# board.net
KiCad netlist of a schematic drawn in EasyEDA Pro
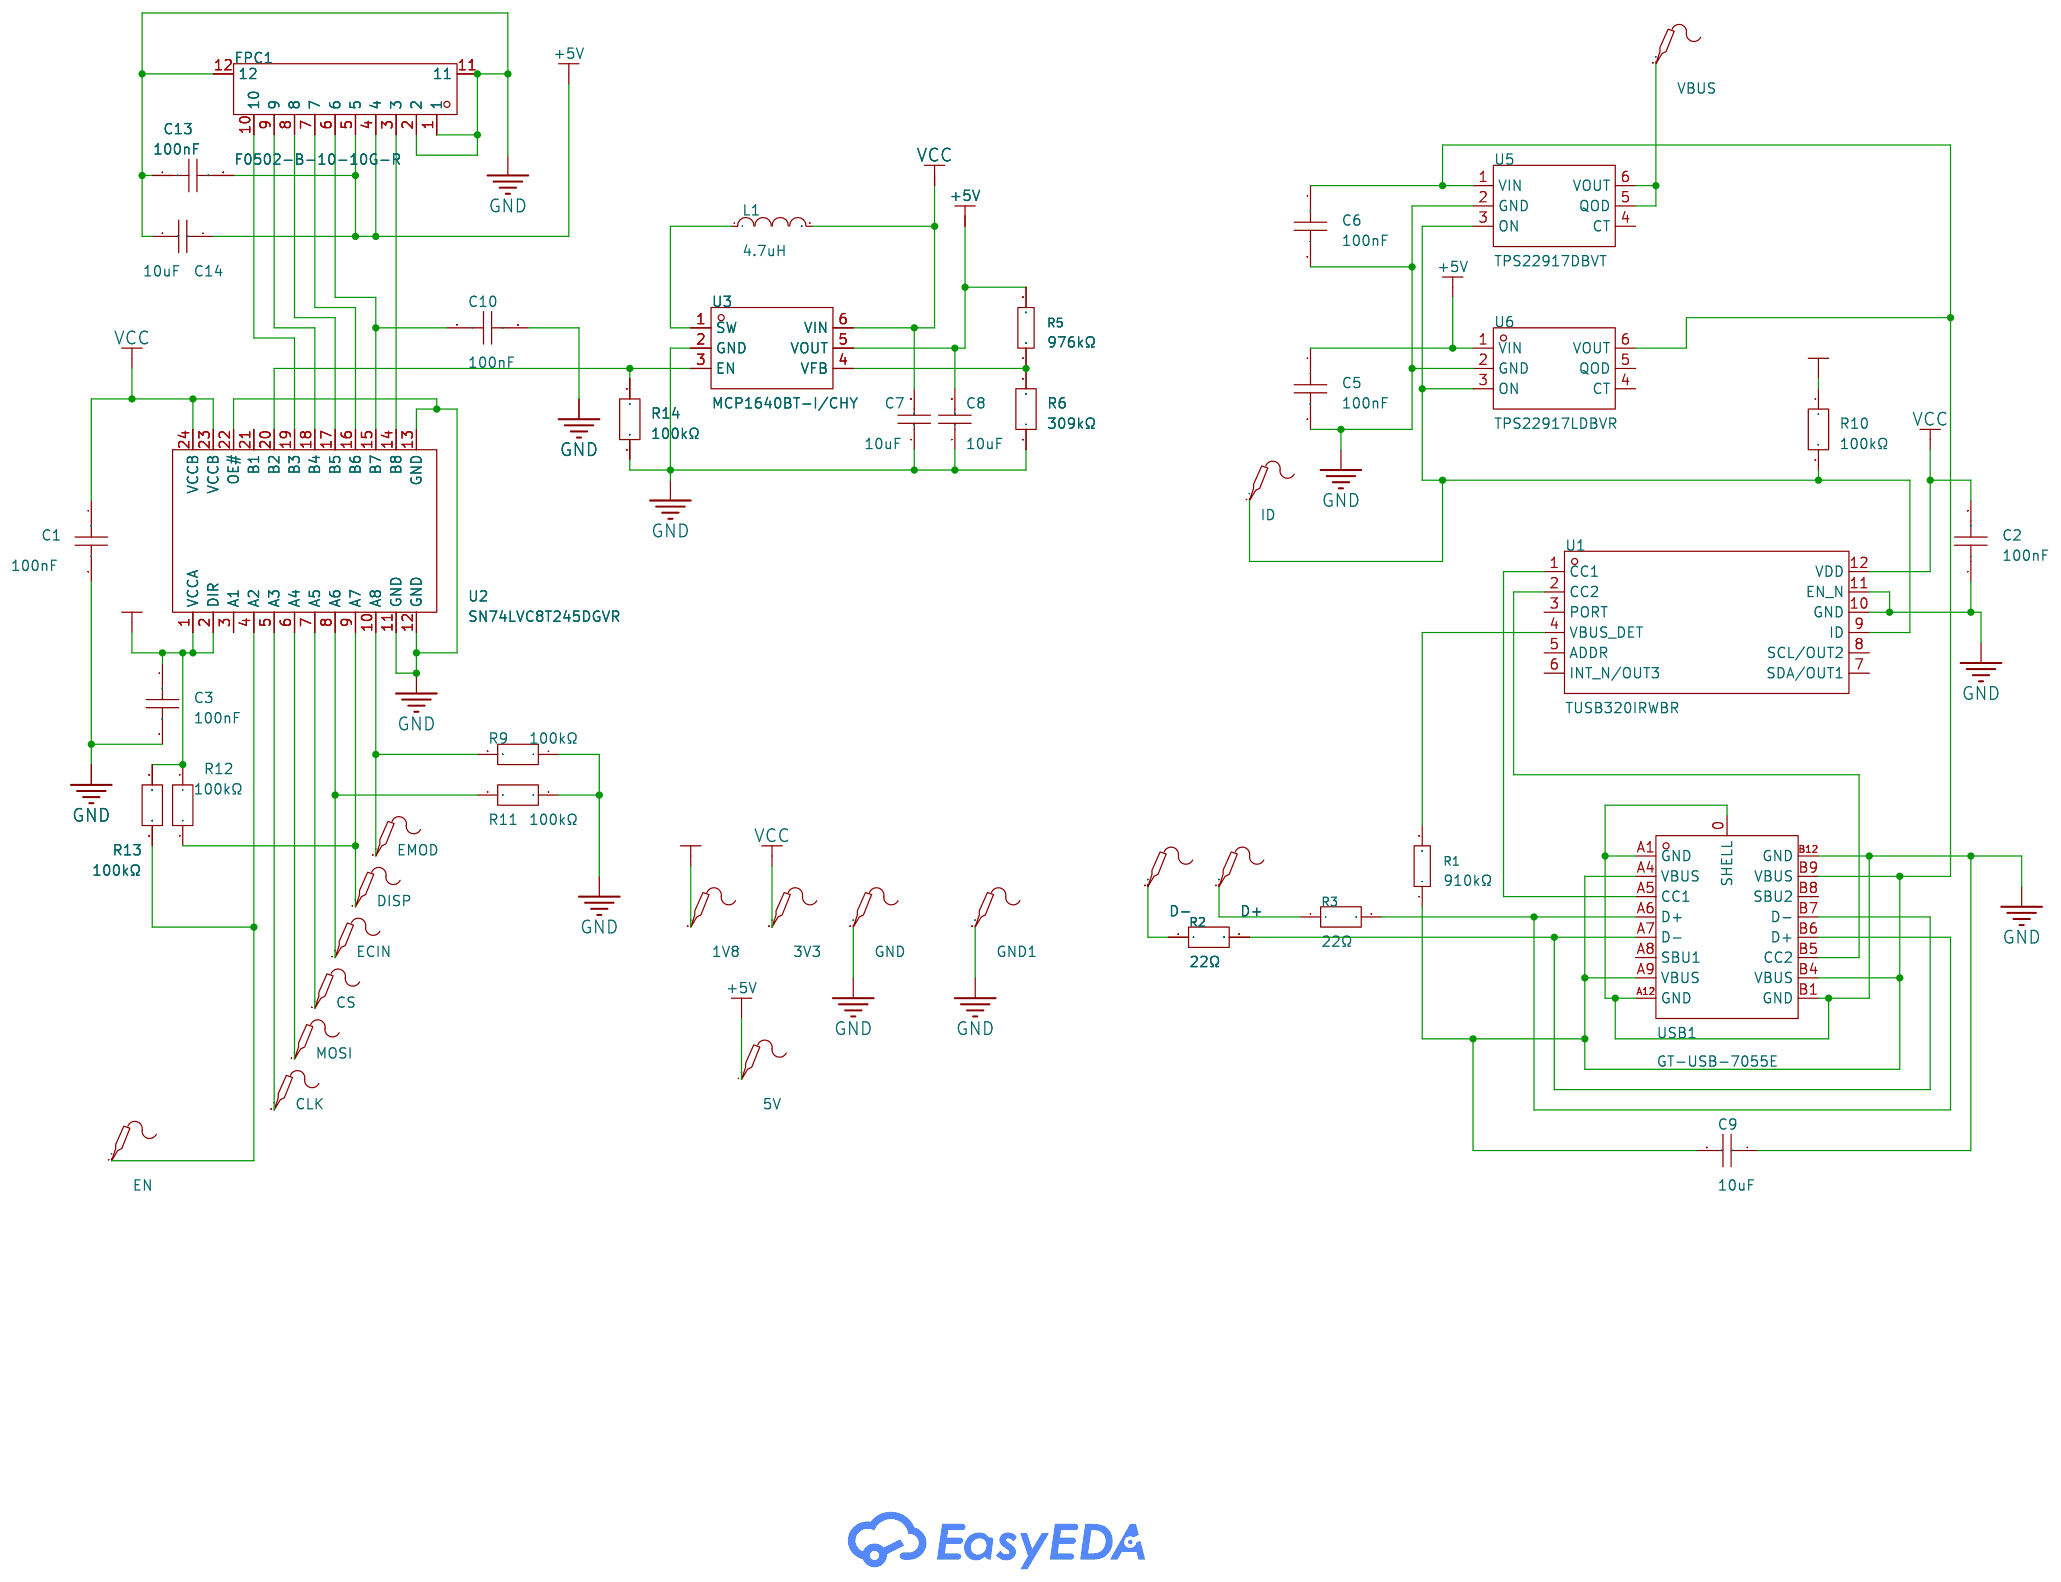
[diagram p0: schematic sheet]

(export (version "E")
  (design (tool "Eeschema 10.0.6"))
  (components
    (comp (ref "1V8")
      (value "~")
      (footprint "easyedapro:Test-Point-0.5mm")
      (description "Test Point 测试点")
      (libsource (lib "easyedapro") (part "Test-Point"))
    )
    (comp (ref "3V3")
      (value "~")
      (footprint "easyedapro:Test-Point-0.5mm")
      (description "Test Point 测试点")
      (libsource (lib "easyedapro") (part "Test-Point"))
    )
    (comp (ref "5V")
      (value "~")
      (footprint "easyedapro:Test-Point-0.5mm")
      (description "Test Point 测试点")
      (libsource (lib "easyedapro") (part "Test-Point"))
    )
    (comp (ref "C1")
      (value "100nF")
      (footprint "easyedapro:C0402")
      (description "Capacitance:100nF Tolerance:±10% Tolerance:±10% Voltage Rating:16V Temperature Coefficient:X7R")
      (fields
        (field (name "Manufacturer Part") "CL05B104KO5NNNC")
        (field (name "Manufacturer") "SAMSUNG(三星)")
      )
      (libsource (lib "easyedapro") (part "CL05B104KO5NNNC"))
    )
    (comp (ref "C2")
      (value "100nF")
      (footprint "easyedapro:C0402")
      (description "Capacitance:100nF Tolerance:±10% Tolerance:±10% Voltage Rating:16V Temperature Coefficient:X7R")
      (fields
        (field (name "Manufacturer Part") "CL05B104KO5NNNC")
        (field (name "Manufacturer") "SAMSUNG(三星)")
      )
      (libsource (lib "easyedapro") (part "CL05B104KO5NNNC"))
    )
    (comp (ref "C3")
      (value "100nF")
      (footprint "easyedapro:C0402")
      (description "Capacitance:100nF Tolerance:±10% Tolerance:±10% Voltage Rating:16V Temperature Coefficient:X7R")
      (fields
        (field (name "Manufacturer Part") "CL05B104KO5NNNC")
        (field (name "Manufacturer") "SAMSUNG(三星)")
      )
      (libsource (lib "easyedapro") (part "CL05B104KO5NNNC"))
    )
    (comp (ref "C5")
      (value "100nF")
      (footprint "easyedapro:C0402")
      (description "Capacitance:100nF Tolerance:±10% Tolerance:±10% Voltage Rating:16V Temperature Coefficient:X7R")
      (fields
        (field (name "Manufacturer Part") "CL05B104KO5NNNC")
        (field (name "Manufacturer") "SAMSUNG(三星)")
      )
      (libsource (lib "easyedapro") (part "CL05B104KO5NNNC"))
    )
    (comp (ref "C6")
      (value "100nF")
      (footprint "easyedapro:C0402")
      (description "Capacitance:100nF Tolerance:±10% Tolerance:±10% Voltage Rating:16V Temperature Coefficient:X7R")
      (fields
        (field (name "Manufacturer Part") "CL05B104KO5NNNC")
        (field (name "Manufacturer") "SAMSUNG(三星)")
      )
      (libsource (lib "easyedapro") (part "CL05B104KO5NNNC"))
    )
    (comp (ref "C7")
      (value "10uF")
      (footprint "easyedapro:C0402")
      (description "Capacitance:10uF Tolerance:±20% Tolerance:±20% Voltage Rating:6.3V Temperature Coefficient:X5R")
      (fields
        (field (name "Manufacturer Part") "CL05A106MQ5NUNC")
        (field (name "Manufacturer") "SAMSUNG(三星)")
      )
      (libsource (lib "easyedapro") (part "CL05A106MQ5NUNC"))
    )
    (comp (ref "C8")
      (value "10uF")
      (footprint "easyedapro:C0402")
      (description "Capacitance:10uF Tolerance:±20% Tolerance:±20% Voltage Rating:6.3V Temperature Coefficient:X5R")
      (fields
        (field (name "Manufacturer Part") "CL05A106MQ5NUNC")
        (field (name "Manufacturer") "SAMSUNG(三星)")
      )
      (libsource (lib "easyedapro") (part "CL05A106MQ5NUNC"))
    )
    (comp (ref "C9")
      (value "10uF")
      (footprint "easyedapro:C0402")
      (description "Capacitance:10uF Tolerance:±20% Tolerance:±20% Voltage Rating:6.3V Temperature Coefficient:X5R")
      (fields
        (field (name "Manufacturer Part") "CL05A106MQ5NUNC")
        (field (name "Manufacturer") "SAMSUNG(三星)")
      )
      (libsource (lib "easyedapro") (part "CL05A106MQ5NUNC"))
    )
    (comp (ref "C10")
      (value "100nF")
      (footprint "easyedapro:C0402")
      (description "Capacitance:100nF Tolerance:±10% Tolerance:±10% Voltage Rating:16V Temperature Coefficient:X7R")
      (fields
        (field (name "Manufacturer Part") "CL05B104KO5NNNC")
        (field (name "Manufacturer") "SAMSUNG(三星)")
      )
      (libsource (lib "easyedapro") (part "CL05B104KO5NNNC"))
    )
    (comp (ref "C13")
      (value "100nF")
      (footprint "easyedapro:C0402")
      (description "Capacitance:100nF Tolerance:±10% Tolerance:±10% Voltage Rating:16V Temperature Coefficient:X7R")
      (fields
        (field (name "Manufacturer Part") "CL05B104KO5NNNC")
        (field (name "Manufacturer") "SAMSUNG(三星)")
      )
      (libsource (lib "easyedapro") (part "CL05B104KO5NNNC"))
    )
    (comp (ref "C14")
      (value "10uF")
      (footprint "easyedapro:C0402")
      (description "Capacitance:10uF Tolerance:±20% Tolerance:±20% Voltage Rating:6.3V Temperature Coefficient:X5R")
      (fields
        (field (name "Manufacturer Part") "CL05A106MQ5NUNC")
        (field (name "Manufacturer") "SAMSUNG(三星)")
      )
      (libsource (lib "easyedapro") (part "CL05A106MQ5NUNC"))
    )
    (comp (ref "CLK")
      (value "~")
      (footprint "easyedapro:Test-Point-0.5mm")
      (description "Test Point 测试点")
      (libsource (lib "easyedapro") (part "Test-Point"))
    )
    (comp (ref "CS")
      (value "~")
      (footprint "easyedapro:Test-Point-0.5mm")
      (description "Test Point 测试点")
      (libsource (lib "easyedapro") (part "Test-Point"))
    )
    (comp (ref "D+")
      (value "~")
      (footprint "easyedapro:Test-Point-0.5mm")
      (description "Test Point 测试点")
      (libsource (lib "easyedapro") (part "Test-Point"))
    )
    (comp (ref "D-")
      (value "~")
      (footprint "easyedapro:Test-Point-0.5mm")
      (description "Test Point 测试点")
      (libsource (lib "easyedapro") (part "Test-Point"))
    )
    (comp (ref "DISP")
      (value "~")
      (footprint "easyedapro:Test-Point-0.5mm")
      (description "Test Point 测试点")
      (libsource (lib "easyedapro") (part "Test-Point"))
    )
    (comp (ref "ECIN")
      (value "~")
      (footprint "easyedapro:Test-Point-0.5mm")
      (description "Test Point 测试点")
      (libsource (lib "easyedapro") (part "Test-Point"))
    )
    (comp (ref "EMOD")
      (value "~")
      (footprint "easyedapro:Test-Point-0.5mm")
      (description "Test Point 测试点")
      (libsource (lib "easyedapro") (part "Test-Point"))
    )
    (comp (ref "EN")
      (value "~")
      (footprint "easyedapro:Test-Point-0.5mm")
      (description "Test Point 测试点")
      (libsource (lib "easyedapro") (part "Test-Point"))
    )
    (comp (ref "FPC1")
      (value "F0502-B-10-10G-R")
      (footprint "easyedapro:FPC-SMD_F0502-B-10-10G-R")
      (fields (field (name "Manufacturer") "XFCN(兴飞)"))
      (libsource (lib "easyedapro") (part "F0502-B-10-10G-R"))
    )
    (comp (ref "GND")
      (value "~")
      (footprint "easyedapro:Test-Point-0.5mm")
      (description "Test Point 测试点")
      (libsource (lib "easyedapro") (part "Test-Point"))
    )
    (comp (ref "GND1")
      (value "~")
      (footprint "easyedapro:Test-Point-0.5mm")
      (description "Test Point 测试点")
      (libsource (lib "easyedapro") (part "Test-Point"))
    )
    (comp (ref "ID")
      (value "~")
      (footprint "easyedapro:Test-Point-0.5mm")
      (description "Test Point 测试点")
      (libsource (lib "easyedapro") (part "Test-Point"))
    )
    (comp (ref "L1")
      (value "4.7uH")
      (footprint "easyedapro:IND-SMD_L4.0-W4.0_FNR40XXS")
      (fields (field (name "Manufacturer Part") "FNR4030S4R7MT") (field (name "Manufacturer") "cjiang(长江微电)"))
      (libsource (lib "easyedapro") (part "FNR4030S4R7MT"))
    )
    (comp (ref "MOSI")
      (value "~")
      (footprint "easyedapro:Test-Point-0.5mm")
      (description "Test Point 测试点")
      (libsource (lib "easyedapro") (part "Test-Point"))
    )
    (comp (ref "R1")
      (value "910kΩ")
      (footprint "easyedapro:R0402")
      (fields
        (field (name "Manufacturer Part") "0402WGF9103TCE")
        (field (name "Manufacturer") "UNI-ROYAL(厚声)")
      )
      (libsource (lib "easyedapro") (part "0402WGF9103TCE"))
    )
    (comp (ref "R2")
      (value "22Ω")
      (footprint "easyedapro:R0402")
      (fields (field (name "Manufacturer Part") "FRC0402J220 TS") (field (name "Manufacturer") "FOJAN(富捷)"))
      (libsource (lib "easyedapro") (part "FRC0402J220 TS"))
    )
    (comp (ref "R3")
      (value "22Ω")
      (footprint "easyedapro:R0402")
      (fields (field (name "Manufacturer Part") "FRC0402J220 TS") (field (name "Manufacturer") "FOJAN(富捷)"))
      (libsource (lib "easyedapro") (part "FRC0402J220 TS"))
    )
    (comp (ref "R5")
      (value "976kΩ")
      (footprint "easyedapro:R0402")
      (fields
        (field (name "Manufacturer Part") "0402WGF9763TCE")
        (field (name "Manufacturer") "UNI-ROYAL(厚声)")
      )
      (libsource (lib "easyedapro") (part "0402WGF9763TCE"))
    )
    (comp (ref "R6")
      (value "309kΩ")
      (footprint "easyedapro:R0402")
      (fields (field (name "Manufacturer Part") "FRC0402F3093TS") (field (name "Manufacturer") "FOJAN(富捷)"))
      (libsource (lib "easyedapro") (part "FRC0402F3093TS"))
    )
    (comp (ref "R9")
      (value "100kΩ")
      (footprint "easyedapro:R0402")
      (fields (field (name "Manufacturer Part") "FRC0402F1003TS") (field (name "Manufacturer") "FOJAN(富捷)"))
      (libsource (lib "easyedapro") (part "FRC0402F1003TS"))
    )
    (comp (ref "R10")
      (value "100kΩ")
      (footprint "easyedapro:R0402")
      (fields (field (name "Manufacturer Part") "FRC0402F1003TS") (field (name "Manufacturer") "FOJAN(富捷)"))
      (libsource (lib "easyedapro") (part "FRC0402F1003TS"))
    )
    (comp (ref "R11")
      (value "100kΩ")
      (footprint "easyedapro:R0402")
      (fields (field (name "Manufacturer Part") "FRC0402F1003TS") (field (name "Manufacturer") "FOJAN(富捷)"))
      (libsource (lib "easyedapro") (part "FRC0402F1003TS"))
    )
    (comp (ref "R12")
      (value "100kΩ")
      (footprint "easyedapro:R0402")
      (fields (field (name "Manufacturer Part") "FRC0402F1003TS") (field (name "Manufacturer") "FOJAN(富捷)"))
      (libsource (lib "easyedapro") (part "FRC0402F1003TS"))
    )
    (comp (ref "R13")
      (value "100kΩ")
      (footprint "easyedapro:R0402")
      (fields (field (name "Manufacturer Part") "FRC0402F1003TS") (field (name "Manufacturer") "FOJAN(富捷)"))
      (libsource (lib "easyedapro") (part "FRC0402F1003TS"))
    )
    (comp (ref "R14")
      (value "100kΩ")
      (footprint "easyedapro:R0402")
      (fields (field (name "Manufacturer Part") "FRC0402F1003TS") (field (name "Manufacturer") "FOJAN(富捷)"))
      (libsource (lib "easyedapro") (part "FRC0402F1003TS"))
    )
    (comp (ref "U1")
      (value "TUSB320IRWBR")
      (footprint "easyedapro:X2QFN-12_L1.6-W1.6-P0.40-TL")
      (fields (field (name "Manufacturer") "TI(德州仪器)"))
      (libsource (lib "easyedapro") (part "TUSB320IRWBR"))
    )
    (comp (ref "U2")
      (value "SN74LVC8T245DGVR")
      (footprint "easyedapro:TVSOP-24_L5.0-W4.4-P0.40-LS6.4-BL")
      (fields (field (name "Manufacturer") "TI(德州仪器)"))
      (libsource (lib "easyedapro") (part "SN74LVC8T245DGVR"))
    )
    (comp (ref "U3")
      (value "MCP1640BT-I/CHY")
      (footprint "easyedapro:SOT-23-6_L2.9-W1.6-P0.95-LS2.8-BR")
      (fields (field (name "Manufacturer") "MICROCHIP(美国微芯)"))
      (libsource (lib "easyedapro") (part "MCP1640BT-I/CHY"))
    )
    (comp (ref "U5")
      (value "TPS22917DBVT")
      (footprint "easyedapro:SOT-23-6_L2.9-W1.6-P0.95-LS2.8-BR")
      (fields (field (name "Manufacturer") "TI(德州仪器)"))
      (libsource (lib "easyedapro") (part "TPS22917DBVT"))
    )
    (comp (ref "U6")
      (value "TPS22917LDBVR")
      (footprint "easyedapro:SOT-23-6_L2.9-W1.6-P0.95-LS2.8-BR")
      (fields (field (name "Manufacturer") "TI(德州仪器)"))
      (libsource (lib "easyedapro") (part "TPS22917LDBVR"))
    )
    (comp (ref "USB1")
      (value "GT-USB-7055E")
      (footprint "easyedapro:USB-C-SMD_GT-USB-7055E")
      (fields (field (name "Manufacturer") "G-Switch(品赞)"))
      (libsource (lib "easyedapro") (part "GT-USB-7055E"))
    )
    (comp (ref "VBUS")
      (value "~")
      (footprint "easyedapro:Test-Point-0.5mm")
      (description "Test Point 测试点")
      (libsource (lib "easyedapro") (part "Test-Point"))
    )
  )
  (nets
    (net (code "1") (name "+5V") (class "Default")
      (node (ref "5V") (pin "1") (pinfunction "1_1") (pintype "unspecified"))
      (node (ref "C13") (pin "2") (pinfunction "2_2") (pintype "unspecified"))
      (node (ref "C14") (pin "1") (pinfunction "1_1") (pintype "input"))
      (node (ref "C5") (pin "1") (pinfunction "1_1") (pintype "unspecified"))
      (node (ref "C8") (pin "2") (pinfunction "2_2") (pintype "input"))
      (node (ref "FPC1") (pin "4") (pinfunction "4_4") (pintype "unspecified"))
      (node (ref "FPC1") (pin "5") (pinfunction "5_5") (pintype "unspecified"))
      (node (ref "R5") (pin "2") (pinfunction "2_2") (pintype "input"))
      (node (ref "U3") (pin "5") (pinfunction "VOUT_5") (pintype "input"))
      (node (ref "U6") (pin "1") (pinfunction "VIN_1") (pintype "unspecified"))
    )
    (net (code "2") (name "1V8") (class "Default")
      (node (ref "1V8") (pin "1") (pinfunction "1_1") (pintype "unspecified"))
      (node (ref "C3") (pin "1") (pinfunction "1_1") (pintype "unspecified"))
      (node (ref "R10") (pin "1") (pinfunction "1_1") (pintype "unspecified"))
      (node (ref "R12") (pin "1") (pinfunction "1_1") (pintype "unspecified"))
      (node (ref "R13") (pin "1") (pinfunction "1_1") (pintype "unspecified"))
      (node (ref "U2") (pin "1") (pinfunction "VCCA_1") (pintype "unspecified"))
      (node (ref "U2") (pin "2") (pinfunction "DIR_2") (pintype "unspecified"))
    )
    (net (code "3") (name "GND") (class "Default")
      (node (ref "C1") (pin "2") (pinfunction "2_2") (pintype "unspecified"))
      (node (ref "C10") (pin "2") (pinfunction "2_2") (pintype "unspecified"))
      (node (ref "C13") (pin "1") (pinfunction "1_1") (pintype "unspecified"))
      (node (ref "C14") (pin "2") (pinfunction "2_2") (pintype "input"))
      (node (ref "C2") (pin "1") (pinfunction "1_1") (pintype "unspecified"))
      (node (ref "C3") (pin "2") (pinfunction "2_2") (pintype "unspecified"))
      (node (ref "C5") (pin "2") (pinfunction "2_2") (pintype "unspecified"))
      (node (ref "C6") (pin "2") (pinfunction "2_2") (pintype "unspecified"))
      (node (ref "C7") (pin "1") (pinfunction "1_1") (pintype "input"))
      (node (ref "C8") (pin "1") (pinfunction "1_1") (pintype "input"))
      (node (ref "C9") (pin "1") (pinfunction "1_1") (pintype "input"))
      (node (ref "FPC1") (pin "1") (pinfunction "1_1") (pintype "unspecified"))
      (node (ref "FPC1") (pin "11") (pinfunction "11_11") (pintype "unspecified"))
      (node (ref "FPC1") (pin "12") (pinfunction "12_12") (pintype "unspecified"))
      (node (ref "FPC1") (pin "2") (pinfunction "2_2") (pintype "unspecified"))
      (node (ref "GND") (pin "1") (pinfunction "1_1") (pintype "unspecified"))
      (node (ref "GND1") (pin "1") (pinfunction "1_1") (pintype "unspecified"))
      (node (ref "R11") (pin "1") (pinfunction "1_1") (pintype "unspecified"))
      (node (ref "R14") (pin "2") (pinfunction "2_2") (pintype "unspecified"))
      (node (ref "R6") (pin "1") (pinfunction "1_1") (pintype "unspecified"))
      (node (ref "R9") (pin "1") (pinfunction "1_1") (pintype "unspecified"))
      (node (ref "U1") (pin "10") (pinfunction "GND_10") (pintype "unspecified"))
      (node (ref "U1") (pin "11") (pinfunction "EN_N_11") (pintype "unspecified"))
      (node (ref "U2") (pin "11") (pinfunction "GND_11") (pintype "unspecified"))
      (node (ref "U2") (pin "12") (pinfunction "GND_12") (pintype "unspecified"))
      (node (ref "U2") (pin "13") (pinfunction "GND_13") (pintype "unspecified"))
      (node (ref "U2") (pin "22") (pinfunction "OE#_22") (pintype "unspecified"))
      (node (ref "U3") (pin "2") (pinfunction "GND_2") (pintype "input"))
      (node (ref "U5") (pin "2") (pinfunction "GND_2") (pintype "unspecified"))
      (node (ref "U6") (pin "2") (pinfunction "GND_2") (pintype "unspecified"))
      (node (ref "USB1") (pin "0") (pinfunction "SHELL_0") (pintype "unspecified"))
      (node (ref "USB1") (pin "A1") (pinfunction "GND_A1") (pintype "unspecified"))
      (node (ref "USB1") (pin "A12") (pinfunction "GND_A12") (pintype "unspecified"))
      (node (ref "USB1") (pin "B1") (pinfunction "GND_B1") (pintype "unspecified"))
      (node (ref "USB1") (pin "B12") (pinfunction "GND_B12") (pintype "unspecified"))
    )
    (net (code "4") (name "Net-(D+-Pad1)") (class "Default")
      (node (ref "D+") (pin "1") (pinfunction "1_1") (pintype "unspecified"))
      (node (ref "R3") (pin "1") (pinfunction "1_1") (pintype "input"))
    )
    (net (code "5") (name "Net-(D--Pad1)") (class "Default")
      (node (ref "D-") (pin "1") (pinfunction "1_1") (pintype "unspecified"))
      (node (ref "R2") (pin "1") (pinfunction "1_1") (pintype "input"))
    )
    (net (code "6") (name "Net-(R2-Pad2)") (class "Default")
      (node (ref "R2") (pin "2") (pinfunction "2_2") (pintype "input"))
      (node (ref "USB1") (pin "A7") (pinfunction "D-_A7") (pintype "unspecified"))
      (node (ref "USB1") (pin "B7") (pinfunction "D-_B7") (pintype "unspecified"))
    )
    (net (code "7") (name "Net-(R3-Pad2)") (class "Default")
      (node (ref "R3") (pin "2") (pinfunction "2_2") (pintype "input"))
      (node (ref "USB1") (pin "A6") (pinfunction "D+_A6") (pintype "unspecified"))
      (node (ref "USB1") (pin "B6") (pinfunction "D+_B6") (pintype "unspecified"))
    )
    (net (code "8") (name "Net-(U1-CC1)") (class "Default")
      (node (ref "U1") (pin "1") (pinfunction "CC1_1") (pintype "unspecified"))
      (node (ref "USB1") (pin "A5") (pinfunction "CC1_A5") (pintype "unspecified"))
    )
    (net (code "9") (name "Net-(U1-CC2)") (class "Default")
      (node (ref "U1") (pin "2") (pinfunction "CC2_2") (pintype "unspecified"))
      (node (ref "USB1") (pin "B5") (pinfunction "CC2_B5") (pintype "unspecified"))
    )
    (net (code "10") (name "Net-(U1-ID)") (class "Default")
      (node (ref "ID") (pin "1") (pinfunction "1_1") (pintype "unspecified"))
      (node (ref "R10") (pin "2") (pinfunction "2_2") (pintype "unspecified"))
      (node (ref "U1") (pin "9") (pinfunction "ID_9") (pintype "unspecified"))
      (node (ref "U5") (pin "3") (pinfunction "ON_3") (pintype "unspecified"))
      (node (ref "U6") (pin "3") (pinfunction "ON_3") (pintype "unspecified"))
    )
    (net (code "11") (name "Net-(U1-VBUS_DET)") (class "Default")
      (node (ref "R1") (pin "2") (pinfunction "2_2") (pintype "input"))
      (node (ref "U1") (pin "4") (pinfunction "VBUS_DET_4") (pintype "unspecified"))
    )
    (net (code "12") (name "Net-(U2-A2)") (class "Default")
      (node (ref "EN") (pin "1") (pinfunction "1_1") (pintype "unspecified"))
      (node (ref "R13") (pin "2") (pinfunction "2_2") (pintype "unspecified"))
      (node (ref "U2") (pin "4") (pinfunction "A2_4") (pintype "unspecified"))
    )
    (net (code "13") (name "Net-(U2-A3)") (class "Default")
      (node (ref "CLK") (pin "1") (pinfunction "1_1") (pintype "unspecified"))
      (node (ref "U2") (pin "5") (pinfunction "A3_5") (pintype "unspecified"))
    )
    (net (code "14") (name "Net-(U2-A4)") (class "Default")
      (node (ref "MOSI") (pin "1") (pinfunction "1_1") (pintype "unspecified"))
      (node (ref "U2") (pin "6") (pinfunction "A4_6") (pintype "unspecified"))
    )
    (net (code "15") (name "Net-(U2-A5)") (class "Default")
      (node (ref "CS") (pin "1") (pinfunction "1_1") (pintype "unspecified"))
      (node (ref "U2") (pin "7") (pinfunction "A5_7") (pintype "unspecified"))
    )
    (net (code "16") (name "Net-(U2-A6)") (class "Default")
      (node (ref "ECIN") (pin "1") (pinfunction "1_1") (pintype "unspecified"))
      (node (ref "R11") (pin "2") (pinfunction "2_2") (pintype "unspecified"))
      (node (ref "U2") (pin "8") (pinfunction "A6_8") (pintype "unspecified"))
    )
    (net (code "17") (name "Net-(U2-A7)") (class "Default")
      (node (ref "DISP") (pin "1") (pinfunction "1_1") (pintype "unspecified"))
      (node (ref "R12") (pin "2") (pinfunction "2_2") (pintype "unspecified"))
      (node (ref "U2") (pin "9") (pinfunction "A7_9") (pintype "unspecified"))
    )
    (net (code "18") (name "Net-(U2-A8)") (class "Default")
      (node (ref "EMOD") (pin "1") (pinfunction "1_1") (pintype "unspecified"))
      (node (ref "R9") (pin "2") (pinfunction "2_2") (pintype "unspecified"))
      (node (ref "U2") (pin "10") (pinfunction "A8_10") (pintype "unspecified"))
    )
    (net (code "19") (name "Net-(U2-B2)") (class "Default")
      (node (ref "R14") (pin "1") (pinfunction "1_1") (pintype "unspecified"))
      (node (ref "U2") (pin "20") (pinfunction "B2_20") (pintype "unspecified"))
      (node (ref "U3") (pin "3") (pinfunction "EN_3") (pintype "input"))
    )
    (net (code "20") (name "Net-(U2-B3)") (class "Default")
      (node (ref "FPC1") (pin "10") (pinfunction "10_10") (pintype "unspecified"))
      (node (ref "U2") (pin "19") (pinfunction "B3_19") (pintype "unspecified"))
    )
    (net (code "21") (name "Net-(U2-B4)") (class "Default")
      (node (ref "FPC1") (pin "9") (pinfunction "9_9") (pintype "unspecified"))
      (node (ref "U2") (pin "18") (pinfunction "B4_18") (pintype "unspecified"))
    )
    (net (code "22") (name "Net-(U2-B5)") (class "Default")
      (node (ref "FPC1") (pin "8") (pinfunction "8_8") (pintype "unspecified"))
      (node (ref "U2") (pin "17") (pinfunction "B5_17") (pintype "unspecified"))
    )
    (net (code "23") (name "Net-(U2-B6)") (class "Default")
      (node (ref "FPC1") (pin "7") (pinfunction "7_7") (pintype "unspecified"))
      (node (ref "U2") (pin "16") (pinfunction "B6_16") (pintype "unspecified"))
    )
    (net (code "24") (name "Net-(U2-B7)") (class "Default")
      (node (ref "C10") (pin "1") (pinfunction "1_1") (pintype "unspecified"))
      (node (ref "FPC1") (pin "6") (pinfunction "6_6") (pintype "unspecified"))
      (node (ref "U2") (pin "15") (pinfunction "B7_15") (pintype "unspecified"))
    )
    (net (code "25") (name "Net-(U2-B8)") (class "Default")
      (node (ref "FPC1") (pin "3") (pinfunction "3_3") (pintype "unspecified"))
      (node (ref "U2") (pin "14") (pinfunction "B8_14") (pintype "unspecified"))
    )
    (net (code "26") (name "Net-(U3-SW)") (class "Default")
      (node (ref "L1") (pin "1") (pinfunction "1_1") (pintype "unspecified"))
      (node (ref "U3") (pin "1") (pinfunction "SW_1") (pintype "input"))
    )
    (net (code "27") (name "Net-(U3-VFB)") (class "Default")
      (node (ref "R5") (pin "1") (pinfunction "1_1") (pintype "input"))
      (node (ref "R6") (pin "2") (pinfunction "2_2") (pintype "unspecified"))
      (node (ref "U3") (pin "4") (pinfunction "VFB_4") (pintype "input"))
    )
    (net (code "28") (name "Net-(U5-QOD)") (class "Default")
      (node (ref "U5") (pin "5") (pinfunction "QOD_5") (pintype "unspecified"))
      (node (ref "U5") (pin "6") (pinfunction "VOUT_6") (pintype "unspecified"))
      (node (ref "VBUS") (pin "1") (pinfunction "1_1") (pintype "unspecified"))
    )
    (net (code "29") (name "Net-(U5-VIN)") (class "Default")
      (node (ref "C6") (pin "1") (pinfunction "1_1") (pintype "unspecified"))
      (node (ref "C9") (pin "2") (pinfunction "2_2") (pintype "input"))
      (node (ref "R1") (pin "1") (pinfunction "1_1") (pintype "input"))
      (node (ref "U5") (pin "1") (pinfunction "VIN_1") (pintype "unspecified"))
      (node (ref "U6") (pin "6") (pinfunction "VOUT_6") (pintype "unspecified"))
      (node (ref "USB1") (pin "A4") (pinfunction "VBUS_A4") (pintype "unspecified"))
      (node (ref "USB1") (pin "A9") (pinfunction "VBUS_A9") (pintype "unspecified"))
      (node (ref "USB1") (pin "B4") (pinfunction "VBUS_B4") (pintype "unspecified"))
      (node (ref "USB1") (pin "B9") (pinfunction "VBUS_B9") (pintype "unspecified"))
    )
    (net (code "30") (name "VCC") (class "Default")
      (node (ref "3V3") (pin "1") (pinfunction "1_1") (pintype "unspecified"))
      (node (ref "C1") (pin "1") (pinfunction "1_1") (pintype "unspecified"))
      (node (ref "C2") (pin "2") (pinfunction "2_2") (pintype "unspecified"))
      (node (ref "C7") (pin "2") (pinfunction "2_2") (pintype "input"))
      (node (ref "L1") (pin "2") (pinfunction "2_2") (pintype "unspecified"))
      (node (ref "U1") (pin "12") (pinfunction "VDD_12") (pintype "unspecified"))
      (node (ref "U2") (pin "23") (pinfunction "VCCB_23") (pintype "unspecified"))
      (node (ref "U2") (pin "24") (pinfunction "VCCB_24") (pintype "unspecified"))
      (node (ref "U3") (pin "6") (pinfunction "VIN_6") (pintype "input"))
    )
    (net (code "31") (name "unconnected-(U1-ADDR-Pad5)") (class "Default")
      (node (ref "U1") (pin "5") (pinfunction "ADDR_5") (pintype "unspecified"))
    )
    (net (code "32") (name "unconnected-(U1-INT_N{slash}OUT3-Pad6)") (class "Default")
      (node (ref "U1") (pin "6") (pinfunction "INT_N/OUT3_6") (pintype "unspecified"))
    )
    (net (code "33") (name "unconnected-(U1-PORT-Pad3)") (class "Default")
      (node (ref "U1") (pin "3") (pinfunction "PORT_3") (pintype "unspecified"))
    )
    (net (code "34") (name "unconnected-(U1-SCL{slash}OUT2-Pad8)") (class "Default")
      (node (ref "U1") (pin "8") (pinfunction "SCL/OUT2_8") (pintype "unspecified"))
    )
    (net (code "35") (name "unconnected-(U1-SDA{slash}OUT1-Pad7)") (class "Default")
      (node (ref "U1") (pin "7") (pinfunction "SDA/OUT1_7") (pintype "unspecified"))
    )
    (net (code "36") (name "unconnected-(U2-A1-Pad3)") (class "Default")
      (node (ref "U2") (pin "3") (pinfunction "A1_3") (pintype "unspecified"))
    )
    (net (code "37") (name "unconnected-(U2-B1-Pad21)") (class "Default")
      (node (ref "U2") (pin "21") (pinfunction "B1_21") (pintype "unspecified"))
    )
    (net (code "38") (name "unconnected-(U5-CT-Pad4)") (class "Default")
      (node (ref "U5") (pin "4") (pinfunction "CT_4") (pintype "unspecified"))
    )
    (net (code "39") (name "unconnected-(U6-CT-Pad4)") (class "Default")
      (node (ref "U6") (pin "4") (pinfunction "CT_4") (pintype "unspecified"))
    )
    (net (code "40") (name "unconnected-(U6-QOD-Pad5)") (class "Default")
      (node (ref "U6") (pin "5") (pinfunction "QOD_5") (pintype "unspecified"))
    )
    (net (code "41") (name "unconnected-(USB1-SBU1-PadA8)") (class "Default")
      (node (ref "USB1") (pin "A8") (pinfunction "SBU1_A8") (pintype "unspecified"))
    )
    (net (code "42") (name "unconnected-(USB1-SBU2-PadB8)") (class "Default")
      (node (ref "USB1") (pin "B8") (pinfunction "SBU2_B8") (pintype "unspecified"))
    )
  )
)
